# Class_AB.net
KiCad netlist of a schematic drawn in Altium Designer
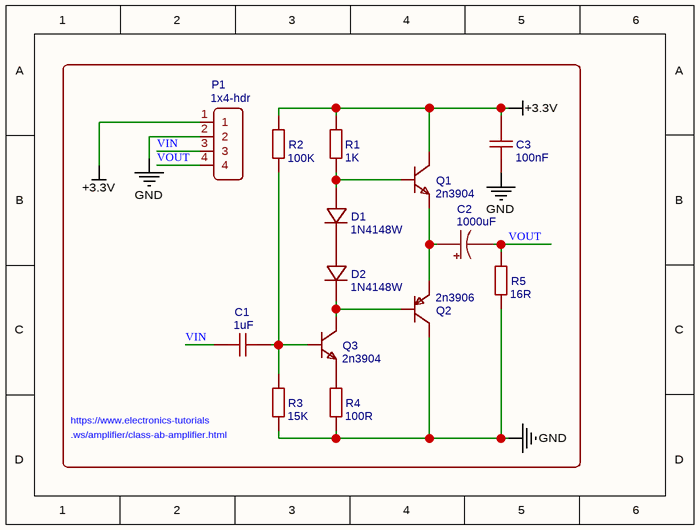
[diagram p0: Class AB.schdoc]

(export (version "E")
  (design (tool "Eeschema 10.0.6"))
  (components
    (comp (ref "C1")
      (value "1uF")
      (fields
        (field (name "BOM_MANUFACTURER PART") "GRM188B31C105KA92D")
        (field (name "BOM_SUPPLIER PART") "C85993")
      )
      (libsource (lib "altium-import") (part "root_0_1uF_"))
    )
    (comp (ref "C2")
      (value "1000uF")
      (fields
        (field (name "BOM_SUPPLIER PART") "C249735")
        (field (name "BOM_MANUFACTURER PART") "VEU102M0J1010-TRO")
        (field (name "CONTRIBUTOR") "LCSC")
      )
      (libsource (lib "altium-import") (part "root_1_1000uF_"))
    )
    (comp (ref "C3")
      (value "100nF")
      (fields
        (field (name "BOM_SUPPLIER PART") "C388001")
        (field (name "BOM_MANUFACTURER PART") "0603B104M500CT")
        (field (name "CONTRIBUTOR") "LCSC")
      )
      (libsource (lib "altium-import") (part "root_2_100nF_"))
    )
    (comp (ref "D1")
      (value "1N4148W")
      (fields (field (name "BOM_SUPPLIER PART") "C109203") (field (name "CONTRIBUTOR") "LCSC"))
      (libsource (lib "altium-import") (part "root_1_1N4148W_"))
    )
    (comp (ref "D2")
      (value "1N4148W")
      (fields (field (name "BOM_SUPPLIER PART") "C109203") (field (name "CONTRIBUTOR") "LCSC"))
      (libsource (lib "altium-import") (part "root_1_1N4148W_"))
    )
    (comp (ref "P1")
      (value "1x4-hdr")
      (fields (field (name "CONTRIBUTOR") "Ezra Wolf"))
      (libsource (lib "altium-import") (part "root_0_1x4-hdr_"))
    )
    (comp (ref "Q1")
      (value "2n3904")
      (fields
        (field (name "BOM_MANUFACTURER PART") "2n3904S-RTK/PS")
        (field (name "BOM_SUPPLIER PART") "C18536")
      )
      (libsource (lib "altium-import") (part "root_0_2n3904_"))
    )
    (comp (ref "Q2")
      (value "2n3906")
      (fields
        (field (name "BOM_MANUFACTURER PART") "2N3906S-RTK/PS")
        (field (name "BOM_SUPPLIER PART") "C147294")
        (field (name "CONTRIBUTOR") "LCSC")
      )
      (libsource (lib "altium-import") (part "root_0_2n3906_"))
    )
    (comp (ref "Q3")
      (value "2n3904")
      (fields
        (field (name "BOM_MANUFACTURER PART") "2n3904S-RTK/PS")
        (field (name "BOM_SUPPLIER PART") "C18536")
      )
      (libsource (lib "altium-import") (part "root_0_2n3904_"))
    )
    (comp (ref "R1")
      (value "1K")
      (fields
        (field (name "BOM_SUPPLIER PART") "C269685")
        (field (name "BOM_MANUFACTURER PART") "RMC06031K5%N")
        (field (name "CONTRIBUTOR") "LCSC")
      )
      (libsource (lib "altium-import") (part "root_1_1K_"))
    )
    (comp (ref "R2")
      (value "100K")
      (fields
        (field (name "BOM_SUPPLIER PART") "C267258")
        (field (name "BOM_MANUFACTURER PART") "R0603RXX104XJ10LTS")
        (field (name "CONTRIBUTOR") "LCSC")
      )
      (libsource (lib "altium-import") (part "root_1_100K_"))
    )
    (comp (ref "R3")
      (value "15K")
      (fields
        (field (name "BOM_SUPPLIER PART") "C269703")
        (field (name "BOM_MANUFACTURER PART") "RMC060315K1%N")
        (field (name "CONTRIBUTOR") "LCSC")
      )
      (libsource (lib "altium-import") (part "root_1_15K_"))
    )
    (comp (ref "R4")
      (value "100R")
      (fields
        (field (name "BOM_SUPPLIER PART") "C209011")
        (field (name "BOM_MANUFACTURER PART") "RMS06FT1000")
        (field (name "CONTRIBUTOR") "LCSC")
      )
      (libsource (lib "altium-import") (part "root_1_100R_"))
    )
    (comp (ref "R5")
      (value "16R")
      (fields
        (field (name "BOM_MANUFACTURER PART") "RTT03160JTP")
        (field (name "BOM_SUPPLIER PART") "C158940")
        (field (name "CONTRIBUTOR") "LCSC")
      )
      (libsource (lib "altium-import") (part "root_1_16R_"))
    )
  )
  (nets
    (net (code "1") (name "+3.3V") (class "Default")
      (node (ref "C3") (pin "1") (pinfunction "1_1") (pintype "passive"))
      (node (ref "P1") (pin "1") (pinfunction "1_1") (pintype "passive"))
      (node (ref "Q1") (pin "3") (pinfunction "C_3") (pintype "passive"))
      (node (ref "R1") (pin "2") (pinfunction "2_2") (pintype "passive"))
      (node (ref "R2") (pin "2") (pinfunction "2_2") (pintype "passive"))
    )
    (net (code "2") (name "/VIN") (class "Default")
      (node (ref "C1") (pin "1") (pinfunction "1_1") (pintype "passive"))
      (node (ref "P1") (pin "3") (pinfunction "3_3") (pintype "passive"))
    )
    (net (code "3") (name "/VOUT") (class "Default")
      (node (ref "C2") (pin "2") (pinfunction "2_2") (pintype "passive"))
      (node (ref "P1") (pin "4") (pinfunction "4_4") (pintype "passive"))
      (node (ref "R5") (pin "1") (pinfunction "1_1") (pintype "passive"))
    )
    (net (code "4") (name "GND") (class "Default")
      (node (ref "C3") (pin "2") (pinfunction "2_2") (pintype "passive"))
      (node (ref "P1") (pin "2") (pinfunction "2_2") (pintype "passive"))
      (node (ref "Q2") (pin "3") (pinfunction "C_3") (pintype "passive"))
      (node (ref "R3") (pin "1") (pinfunction "1_1") (pintype "passive"))
      (node (ref "R4") (pin "1") (pinfunction "1_1") (pintype "passive"))
      (node (ref "R5") (pin "2") (pinfunction "2_2") (pintype "passive"))
    )
    (net (code "5") (name "Net-(D1-A)") (class "Default")
      (node (ref "D1") (pin "2") (pinfunction "A_2") (pintype "passive"))
      (node (ref "Q1") (pin "2") (pinfunction "B_2") (pintype "passive"))
      (node (ref "R1") (pin "1") (pinfunction "1_1") (pintype "passive"))
    )
    (net (code "6") (name "Net-(D1-C)") (class "Default")
      (node (ref "D1") (pin "1") (pinfunction "C_1") (pintype "passive"))
      (node (ref "D2") (pin "2") (pinfunction "A_2") (pintype "passive"))
    )
    (net (code "7") (name "Net-(D2-C)") (class "Default")
      (node (ref "D2") (pin "1") (pinfunction "C_1") (pintype "passive"))
      (node (ref "Q2") (pin "2") (pinfunction "B_2") (pintype "passive"))
      (node (ref "Q3") (pin "3") (pinfunction "C_3") (pintype "passive"))
    )
    (net (code "8") (name "Net-(Q1-E)") (class "Default")
      (node (ref "C2") (pin "1") (pinfunction "1_1") (pintype "passive"))
      (node (ref "Q1") (pin "1") (pinfunction "E_1") (pintype "passive"))
      (node (ref "Q2") (pin "1") (pinfunction "E_1") (pintype "passive"))
    )
    (net (code "9") (name "Net-(Q3-B)") (class "Default")
      (node (ref "C1") (pin "2") (pinfunction "2_2") (pintype "passive"))
      (node (ref "Q3") (pin "2") (pinfunction "B_2") (pintype "passive"))
      (node (ref "R2") (pin "1") (pinfunction "1_1") (pintype "passive"))
      (node (ref "R3") (pin "2") (pinfunction "2_2") (pintype "passive"))
    )
    (net (code "10") (name "Net-(Q3-E)") (class "Default")
      (node (ref "Q3") (pin "1") (pinfunction "E_1") (pintype "passive"))
      (node (ref "R4") (pin "2") (pinfunction "2_2") (pintype "passive"))
    )
  )
)
